# Screen_PCB.net
KiCad netlist of a schematic drawn in Altium Designer
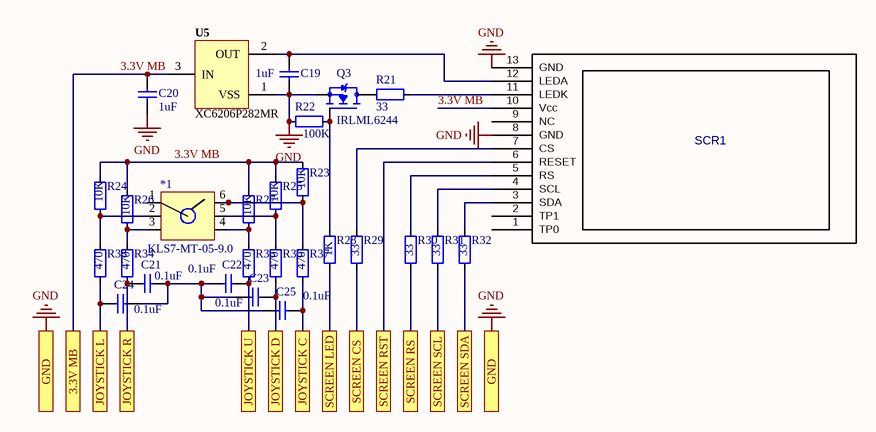
[diagram p0: Screen_PCB.SchDoc]

(export (version "E")
  (design (tool "Eeschema 10.0.6"))
  (components
    (comp (ref "*1")
      (value "KLS7-MT-05-9.0")
      (footprint "KLS7-MT-05-9.0")
      (libsource (lib "V_NB-IoT_3.1") (part "KLS7-MT-05-9.0"))
    )
    (comp (ref "C19") (value "1uF") (footprint "C0805") (libsource (lib "V_NB-IoT_3.1") (part "CAP")))
    (comp (ref "C20") (value "1uF") (footprint "C0805") (libsource (lib "V_NB-IoT_3.1") (part "CAP")))
    (comp (ref "C21") (value "0.1uF") (footprint "R0603") (libsource (lib "V_NB-IoT_3.1") (part "CAP")))
    (comp (ref "C22") (value "0.1uF") (footprint "R0603") (libsource (lib "V_NB-IoT_3.1") (part "CAP")))
    (comp (ref "C23") (value "0.1uF") (footprint "R0603") (libsource (lib "V_NB-IoT_3.1") (part "CAP")))
    (comp (ref "C24") (value "0.1uF") (footprint "R0603") (libsource (lib "V_NB-IoT_3.1") (part "CAP")))
    (comp (ref "C25") (value "0.1uF") (footprint "R0603") (libsource (lib "V_NB-IoT_3.1") (part "CAP")))
    (comp (ref "Q3")
      (value "IRLML6244")
      (footprint "SOT-23")
      (description "MOSFET P-CH 30V 3.6A SOT-23-3")
      (fields
        (field (name "MF") "{'manufacturer': u'Infineon Technologies'}")
        (field (name "MP") "IRLML9301TRPBF")
      )
      (libsource (lib "V_NB-IoT_3.1") (part "IRLML6244"))
    )
    (comp (ref "R21")
      (value "33")
      (footprint "R0603")
      (description "Resistor SMD")
      (libsource (lib "V_NB-IoT_3.1") (part "RES SMD UNI"))
    )
    (comp (ref "R22")
      (value "100K")
      (footprint "R0603")
      (description "Resistor SMD")
      (libsource (lib "V_NB-IoT_3.1") (part "RES SMD UNI"))
    )
    (comp (ref "R23")
      (value "10K")
      (footprint "R0603")
      (description "Resistor SMD")
      (libsource (lib "V_NB-IoT_3.1") (part "RES SMD UNI"))
    )
    (comp (ref "R24")
      (value "10K")
      (footprint "R0603")
      (description "Resistor SMD")
      (libsource (lib "V_NB-IoT_3.1") (part "RES SMD UNI"))
    )
    (comp (ref "R25")
      (value "10K")
      (footprint "R0603")
      (description "Resistor SMD")
      (libsource (lib "V_NB-IoT_3.1") (part "RES SMD UNI"))
    )
    (comp (ref "R26")
      (value "10K")
      (footprint "R0603")
      (description "Resistor SMD")
      (libsource (lib "V_NB-IoT_3.1") (part "RES SMD UNI"))
    )
    (comp (ref "R27")
      (value "10K")
      (footprint "R0603")
      (description "Resistor SMD")
      (libsource (lib "V_NB-IoT_3.1") (part "RES SMD UNI"))
    )
    (comp (ref "R28")
      (value "1K")
      (footprint "R0603")
      (description "Resistor SMD")
      (libsource (lib "V_NB-IoT_3.1") (part "RES SMD UNI"))
    )
    (comp (ref "R29")
      (value "33")
      (footprint "R0603")
      (description "Resistor SMD")
      (libsource (lib "V_NB-IoT_3.1") (part "RES SMD UNI"))
    )
    (comp (ref "R30")
      (value "33")
      (footprint "R0603")
      (description "Resistor SMD")
      (libsource (lib "V_NB-IoT_3.1") (part "RES SMD UNI"))
    )
    (comp (ref "R31")
      (value "33")
      (footprint "R0603")
      (description "Resistor SMD")
      (libsource (lib "V_NB-IoT_3.1") (part "RES SMD UNI"))
    )
    (comp (ref "R32")
      (value "33")
      (footprint "R0603")
      (description "Resistor SMD")
      (libsource (lib "V_NB-IoT_3.1") (part "RES SMD UNI"))
    )
    (comp (ref "R33")
      (value "470")
      (footprint "R0603")
      (description "Resistor SMD")
      (libsource (lib "V_NB-IoT_3.1") (part "RES SMD UNI"))
    )
    (comp (ref "R34")
      (value "470")
      (footprint "R0603")
      (description "Resistor SMD")
      (libsource (lib "V_NB-IoT_3.1") (part "RES SMD UNI"))
    )
    (comp (ref "R35")
      (value "470")
      (footprint "R0603")
      (description "Resistor SMD")
      (libsource (lib "V_NB-IoT_3.1") (part "RES SMD UNI"))
    )
    (comp (ref "R36")
      (value "470")
      (footprint "R0603")
      (description "Resistor SMD")
      (libsource (lib "V_NB-IoT_3.1") (part "RES SMD UNI"))
    )
    (comp (ref "R37")
      (value "470")
      (footprint "R0603")
      (description "Resistor SMD")
      (libsource (lib "V_NB-IoT_3.1") (part "RES SMD UNI"))
    )
    (comp (ref "SCR1")
      (value "0.96INCH_TFT")
      (footprint "0.96INCH_TFT")
      (description "LH096T-IG01 TFT RGB 0,96\" screen")
      (libsource (lib "V_NB-IoT_3.1") (part "0.96INCH_TFT"))
    )
    (comp (ref "U5")
      (value "XC6206P282MR")
      (footprint "SOT95P237X112-3N")
      (fields (field (name "MANUFACTURER") "UTD"))
      (libsource (lib "V_NB-IoT_3.1") (part "XC6206P282MR"))
    )
  )
  (nets
    (net (code "1") (name "/3.3V MB") (class "Default")
      (node (ref "C20") (pin "2") (pinfunction "2_2") (pintype "passive"))
      (node (ref "R23") (pin "1") (pinfunction "1_1") (pintype "passive"))
      (node (ref "R24") (pin "1") (pinfunction "1_1") (pintype "passive"))
      (node (ref "R25") (pin "1") (pinfunction "1_1") (pintype "passive"))
      (node (ref "R26") (pin "1") (pinfunction "1_1") (pintype "passive"))
      (node (ref "R27") (pin "1") (pinfunction "1_1") (pintype "passive"))
      (node (ref "SCR1") (pin "10") (pinfunction "Vcc_10") (pintype "passive"))
      (node (ref "U5") (pin "3") (pinfunction "IN_3") (pintype "passive"))
    )
    (net (code "2") (name "/JOYSTICK C") (class "Default")
      (node (ref "C25") (pin "1") (pinfunction "1_1") (pintype "passive"))
      (node (ref "R37") (pin "2") (pinfunction "2_2") (pintype "passive"))
    )
    (net (code "3") (name "/JOYSTICK D") (class "Default")
      (node (ref "C23") (pin "1") (pinfunction "1_1") (pintype "passive"))
      (node (ref "R36") (pin "2") (pinfunction "2_2") (pintype "passive"))
    )
    (net (code "4") (name "/JOYSTICK L") (class "Default")
      (node (ref "C24") (pin "2") (pinfunction "2_2") (pintype "passive"))
      (node (ref "R33") (pin "2") (pinfunction "2_2") (pintype "passive"))
    )
    (net (code "5") (name "/JOYSTICK R") (class "Default")
      (node (ref "C21") (pin "2") (pinfunction "2_2") (pintype "passive"))
      (node (ref "R34") (pin "2") (pinfunction "2_2") (pintype "passive"))
    )
    (net (code "6") (name "/JOYSTICK U") (class "Default")
      (node (ref "C22") (pin "1") (pinfunction "1_1") (pintype "passive"))
      (node (ref "R35") (pin "2") (pinfunction "2_2") (pintype "passive"))
    )
    (net (code "7") (name "/SCREEN CS") (class "Default")
      (node (ref "R29") (pin "2") (pinfunction "2_2") (pintype "passive"))
    )
    (net (code "8") (name "/SCREEN LED") (class "Default")
      (node (ref "R28") (pin "2") (pinfunction "2_2") (pintype "passive"))
    )
    (net (code "9") (name "/SCREEN RS") (class "Default")
      (node (ref "R30") (pin "2") (pinfunction "2_2") (pintype "passive"))
    )
    (net (code "10") (name "/SCREEN RST") (class "Default")
      (node (ref "SCR1") (pin "6") (pinfunction "RESET_6") (pintype "passive"))
    )
    (net (code "11") (name "/SCREEN SCL") (class "Default")
      (node (ref "R31") (pin "2") (pinfunction "2_2") (pintype "passive"))
    )
    (net (code "12") (name "/SCREEN SDA") (class "Default")
      (node (ref "R32") (pin "2") (pinfunction "2_2") (pintype "passive"))
    )
    (net (code "13") (name "GND") (class "Default")
      (node (ref "C19") (pin "1") (pinfunction "1_1") (pintype "passive"))
      (node (ref "C20") (pin "1") (pinfunction "1_1") (pintype "passive"))
      (node (ref "Q3") (pin "2") (pinfunction "S_2") (pintype "passive"))
      (node (ref "R22") (pin "1") (pinfunction "1_1") (pintype "passive"))
      (node (ref "SCR1") (pin "13") (pinfunction "GND_13") (pintype "passive"))
      (node (ref "SCR1") (pin "8") (pinfunction "GND_8") (pintype "passive"))
      (node (ref "U5") (pin "1") (pinfunction "VSS_1") (pintype "passive"))
    )
    (net (code "14") (name "Net-(*1-Pad2)") (class "Default")
      (node (ref "*1") (pin "2") (pintype "passive"))
      (node (ref "R24") (pin "2") (pinfunction "2_2") (pintype "passive"))
      (node (ref "R33") (pin "1") (pinfunction "1_1") (pintype "passive"))
    )
    (net (code "15") (name "Net-(*1-Pad3)") (class "Default")
      (node (ref "*1") (pin "3") (pintype "passive"))
      (node (ref "R26") (pin "2") (pinfunction "2_2") (pintype "passive"))
      (node (ref "R34") (pin "1") (pinfunction "1_1") (pintype "passive"))
    )
    (net (code "16") (name "Net-(*1-Pad4)") (class "Default")
      (node (ref "*1") (pin "4") (pintype "passive"))
      (node (ref "R27") (pin "2") (pinfunction "2_2") (pintype "passive"))
      (node (ref "R35") (pin "1") (pinfunction "1_1") (pintype "passive"))
    )
    (net (code "17") (name "Net-(*1-Pad5)") (class "Default")
      (node (ref "*1") (pin "5") (pintype "passive"))
      (node (ref "R25") (pin "2") (pinfunction "2_2") (pintype "passive"))
      (node (ref "R36") (pin "1") (pinfunction "1_1") (pintype "passive"))
    )
    (net (code "18") (name "Net-(*1-Pad6)") (class "Default")
      (node (ref "*1") (pin "6") (pintype "passive"))
      (node (ref "R23") (pin "2") (pinfunction "2_2") (pintype "passive"))
      (node (ref "R37") (pin "1") (pinfunction "1_1") (pintype "passive"))
    )
    (net (code "19") (name "Net-(C21-Pad1)") (class "Default")
      (node (ref "C21") (pin "1") (pinfunction "1_1") (pintype "passive"))
      (node (ref "C22") (pin "2") (pinfunction "2_2") (pintype "passive"))
      (node (ref "C23") (pin "2") (pinfunction "2_2") (pintype "passive"))
      (node (ref "C24") (pin "1") (pinfunction "1_1") (pintype "passive"))
      (node (ref "C25") (pin "2") (pinfunction "2_2") (pintype "passive"))
    )
    (net (code "20") (name "Net-(Q3-D)") (class "Default")
      (node (ref "Q3") (pin "3") (pinfunction "D_3") (pintype "passive"))
      (node (ref "R21") (pin "2") (pinfunction "2_2") (pintype "passive"))
    )
    (net (code "21") (name "Net-(Q3-G)") (class "Default")
      (node (ref "Q3") (pin "1") (pinfunction "G_1") (pintype "passive"))
      (node (ref "R22") (pin "2") (pinfunction "2_2") (pintype "passive"))
      (node (ref "R28") (pin "1") (pinfunction "1_1") (pintype "passive"))
    )
    (net (code "22") (name "Net-(SCR1-CS)") (class "Default")
      (node (ref "R29") (pin "1") (pinfunction "1_1") (pintype "passive"))
      (node (ref "SCR1") (pin "7") (pinfunction "CS_7") (pintype "passive"))
    )
    (net (code "23") (name "Net-(SCR1-LEDA)") (class "Default")
      (node (ref "C19") (pin "2") (pinfunction "2_2") (pintype "passive"))
      (node (ref "SCR1") (pin "12") (pinfunction "LEDA_12") (pintype "passive"))
      (node (ref "U5") (pin "2") (pinfunction "OUT_2") (pintype "power_in"))
    )
    (net (code "24") (name "Net-(SCR1-LEDK)") (class "Default")
      (node (ref "R21") (pin "1") (pinfunction "1_1") (pintype "passive"))
      (node (ref "SCR1") (pin "11") (pinfunction "LEDK_11") (pintype "passive"))
    )
    (net (code "25") (name "Net-(SCR1-RS)") (class "Default")
      (node (ref "R30") (pin "1") (pinfunction "1_1") (pintype "passive"))
      (node (ref "SCR1") (pin "5") (pinfunction "RS_5") (pintype "passive"))
    )
    (net (code "26") (name "Net-(SCR1-SCL)") (class "Default")
      (node (ref "R31") (pin "1") (pinfunction "1_1") (pintype "passive"))
      (node (ref "SCR1") (pin "4") (pinfunction "SCL_4") (pintype "passive"))
    )
    (net (code "27") (name "Net-(SCR1-SDA)") (class "Default")
      (node (ref "R32") (pin "1") (pinfunction "1_1") (pintype "passive"))
      (node (ref "SCR1") (pin "3") (pinfunction "SDA_3") (pintype "passive"))
    )
    (net (code "28") (name "unconnected-(*1-Pad1)") (class "Default")
      (node (ref "*1") (pin "1") (pintype "passive"))
    )
    (net (code "29") (name "unconnected-(SCR1-NC-Pad9)") (class "Default")
      (node (ref "SCR1") (pin "9") (pinfunction "NC_9") (pintype "passive"))
    )
    (net (code "30") (name "unconnected-(SCR1-TP0-Pad1)") (class "Default")
      (node (ref "SCR1") (pin "1") (pinfunction "TP0_1") (pintype "passive"))
    )
    (net (code "31") (name "unconnected-(SCR1-TP1-Pad2)") (class "Default")
      (node (ref "SCR1") (pin "2") (pinfunction "TP1_2") (pintype "passive"))
    )
  )
)
